# 51-2001-01-14_04_Power_Module_Schematic.net
KiCad netlist of a schematic drawn in Altium Designer
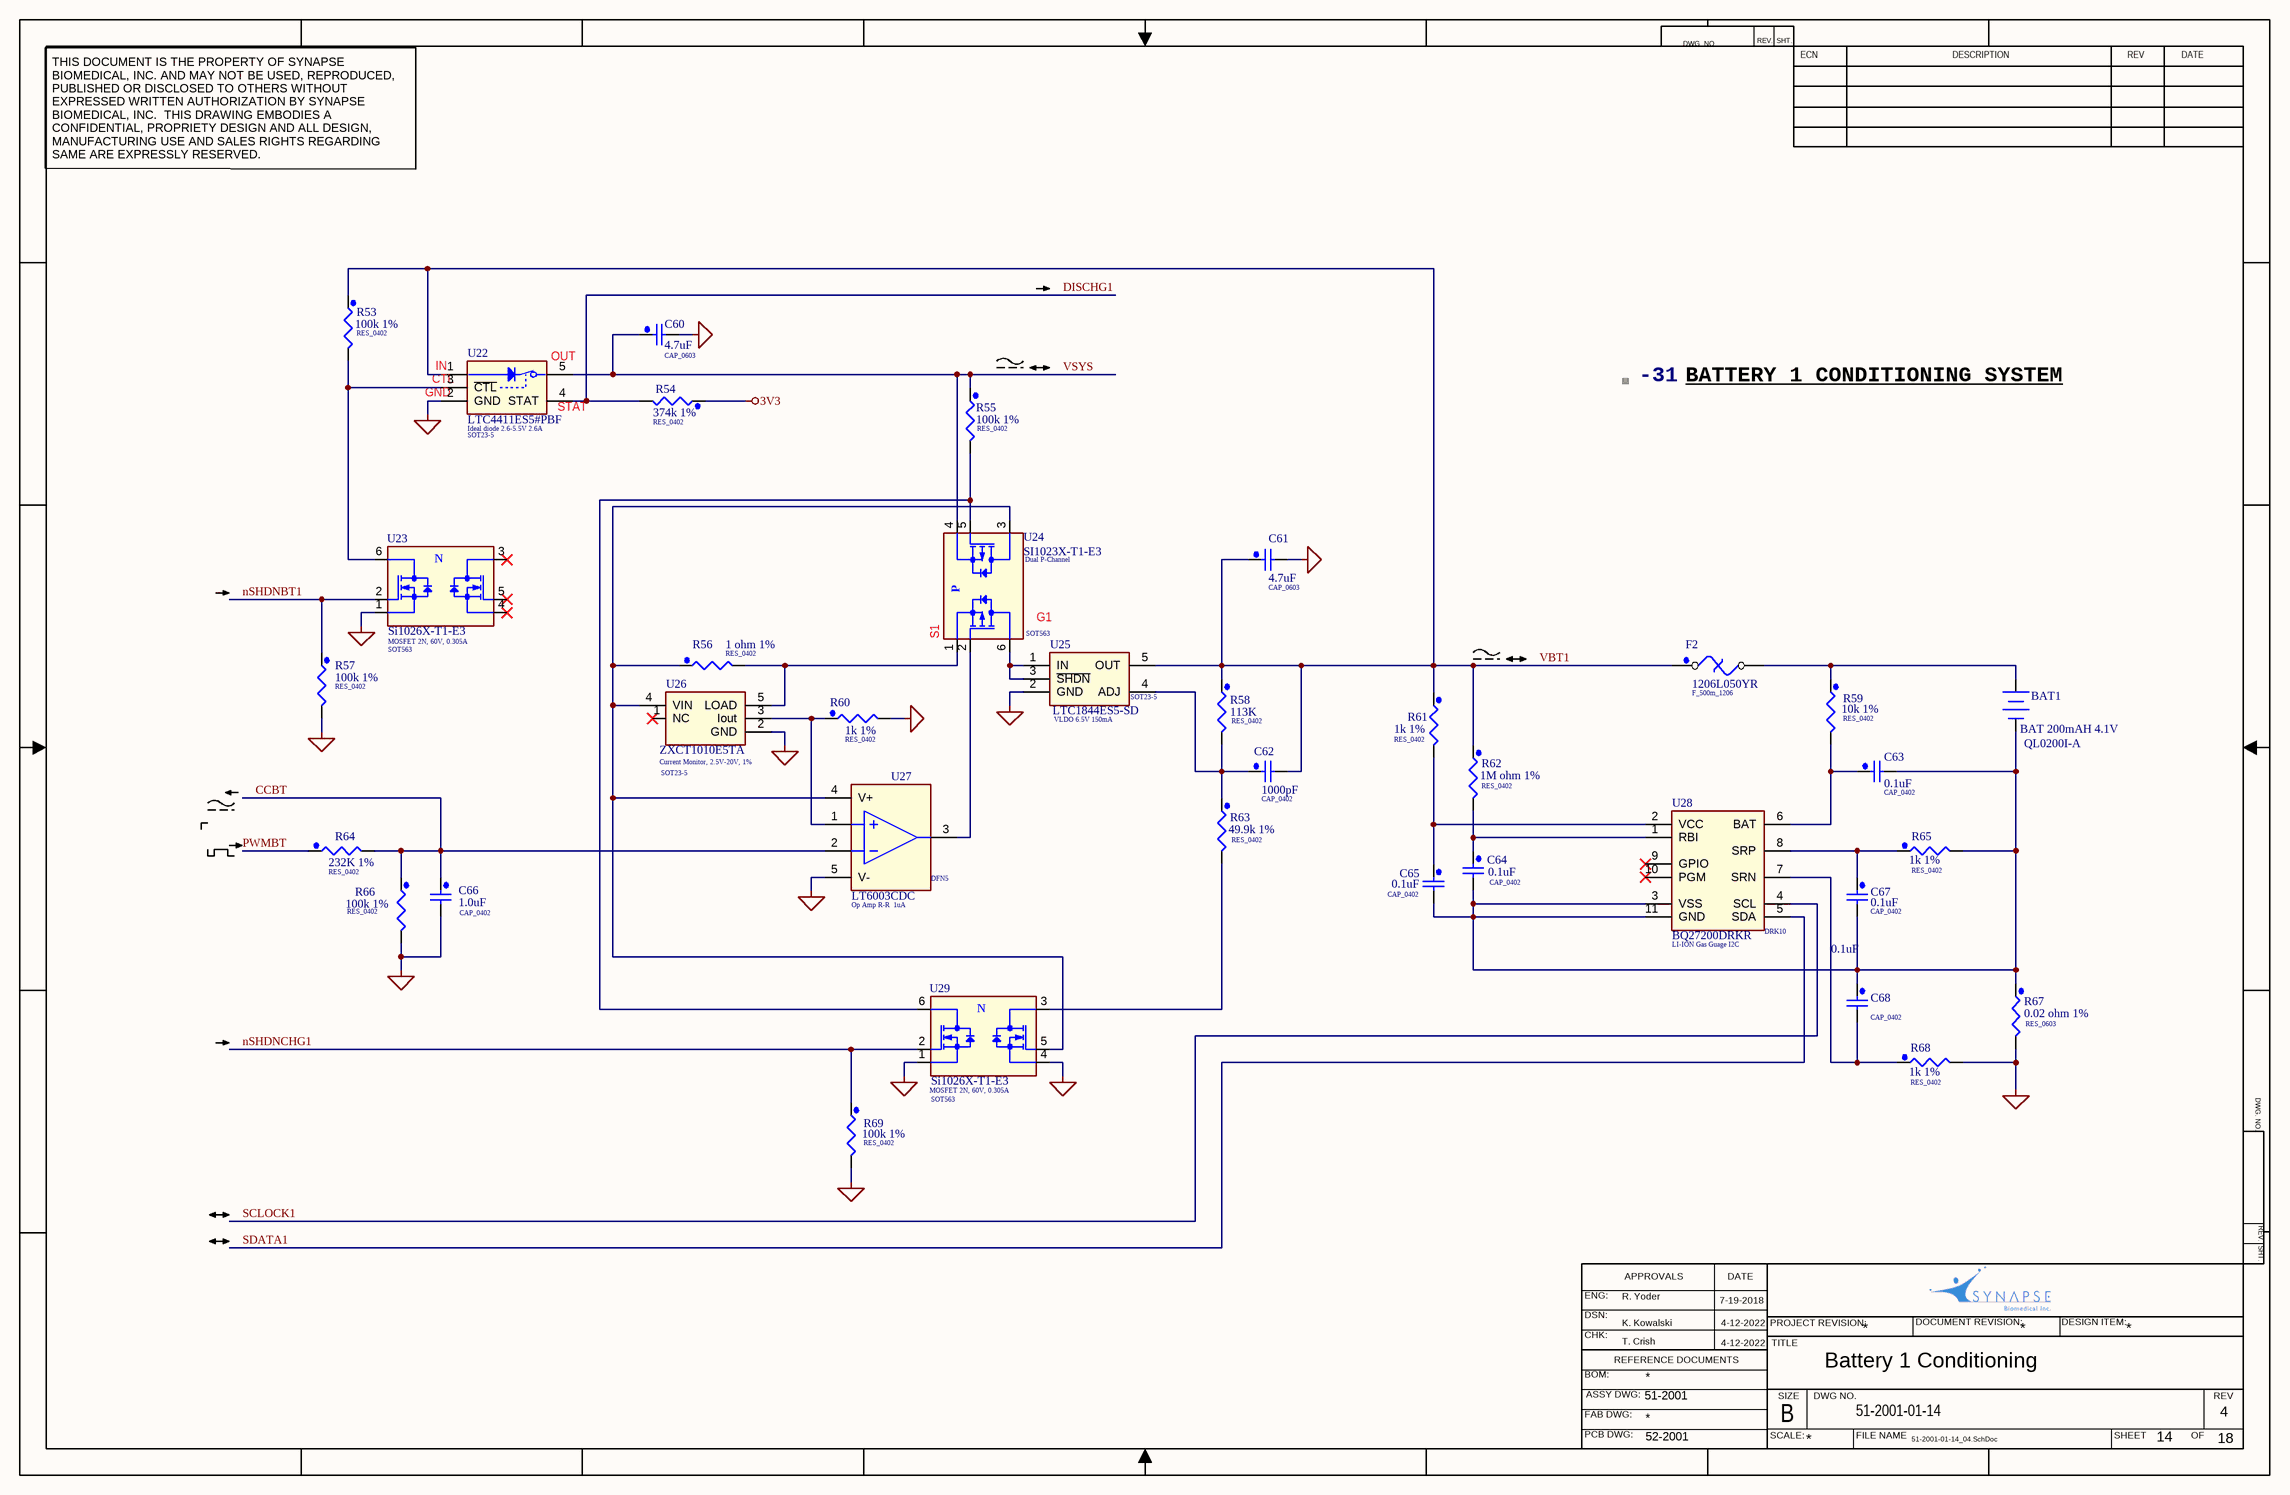
[diagram p0: 51-2001-01-14_04 Power Module Schematic.SchDoc]

(export (version "E")
  (design (tool "Eeschema 10.0.6"))
  (components
    (comp (ref "-31")
      (value "BOM_S1")
      (description "BOM item small graphic")
      (fields (field (name "XDESCRIPTION") "BATTERY 1 CONDITIONING SYSTEM"))
      (libsource (lib "BOM_sym") (part "BOM_S1"))
    )
    (comp (ref "BAT1")
      (value "BAT 200mAH 4.1V")
      (footprint "QL0200I-A")
      (description "Li-ion battery 200mAH 4.1V")
      (fields (field (name "MFR") "Quallion") (field (name "MPN") "QL0200I-A"))
      (libsource (lib "NNPS Integrated Parts") (part "QL0200I-A"))
    )
    (comp (ref "C60")
      (value "4.7uF")
      (footprint "CAP_0603")
      (description "4.7uF, 10V, X5R, 10%, 0603, RoHS")
      (fields
        (field (name "MFR") "Murata Electronics North America")
        (field (name "PACKAGEDESCRIPTION") "CAP_0603")
        (field (name "MPN") "GRM185R61A475KE11D")
      )
      (libsource (lib "NNPS Integrated Parts") (part "LMK107BJ475KA-T"))
    )
    (comp (ref "C61")
      (value "4.7uF")
      (footprint "CAP_0603")
      (description "4.7uF, 10V, X5R, 10%, 0603, RoHS")
      (fields
        (field (name "MFR") "Murata Electronics North America")
        (field (name "PACKAGEDESCRIPTION") "CAP_0603")
        (field (name "MPN") "GRM185R61A475KE11D")
      )
      (libsource (lib "NNPS Integrated Parts") (part "LMK107BJ475KA-T"))
    )
    (comp (ref "C62")
      (value "1000pF")
      (footprint "CAP_0402")
      (description "1000pF, 50V, C0G, 5%, 0402, RoHS")
      (fields
        (field (name "MFR") "Murata")
        (field (name "PACKAGEDESCRIPTION") "CAP_0402")
        (field (name "MPN") "GRM1555C1H102JA01D")
      )
      (libsource (lib "NNPS Integrated Parts") (part "GRM1555C1H102JA01D"))
    )
    (comp (ref "C63")
      (value "0.1uF")
      (footprint "CAP_0402")
      (description "0.1uF, 16V, X7R, 0402, RoHS")
      (fields
        (field (name "MFR") "Murata")
        (field (name "PACKAGEDESCRIPTION") "CAP_0402")
        (field (name "MPN") "GRM155R71C104KA88D")
      )
      (libsource (lib "NNPS Integrated Parts") (part "GRM155R71C104KA88D"))
    )
    (comp (ref "C64")
      (value "0.1uF")
      (footprint "CAP_0402")
      (description "0.1uF, 16V, X7R, 0402, RoHS")
      (fields
        (field (name "MFR") "Murata")
        (field (name "PACKAGEDESCRIPTION") "CAP_0402")
        (field (name "MPN") "GRM155R71C104KA88D")
      )
      (libsource (lib "NNPS Integrated Parts") (part "GRM155R71C104KA88D"))
    )
    (comp (ref "C65")
      (value "0.1uF")
      (footprint "CAP_0402")
      (description "0.1uF, 16V, X7R, 0402, RoHS")
      (fields
        (field (name "MFR") "Murata")
        (field (name "PACKAGEDESCRIPTION") "CAP_0402")
        (field (name "MPN") "GRM155R71C104KA88D")
      )
      (libsource (lib "NNPS Integrated Parts") (part "GRM155R71C104KA88D"))
    )
    (comp (ref "C66")
      (value "1.0uF")
      (footprint "CAP_0402")
      (description "1.0uF, 6.3V, X5R, 20%, 0402, RoHS")
      (fields
        (field (name "MFR") "Murata Electronics North America")
        (field (name "PACKAGEDESCRIPTION") "CAP_0402")
        (field (name "MPN") "GRM152R60J105ME15D")
      )
      (libsource (lib "NNPS Integrated Parts") (part "ECJ-0EB0J105M"))
    )
    (comp (ref "C67")
      (value "0.1uF")
      (footprint "CAP_0402")
      (description "0.1uF, 16V, X7R, 0402, RoHS")
      (fields
        (field (name "MFR") "Murata")
        (field (name "PACKAGEDESCRIPTION") "CAP_0402")
        (field (name "MPN") "GRM155R71C104KA88D")
      )
      (libsource (lib "NNPS Integrated Parts") (part "GRM155R71C104KA88D"))
    )
    (comp (ref "C68")
      (value "0.1uF")
      (footprint "CAP_0402")
      (description "0.1uF, 16V, X7R, 0402, RoHS")
      (fields
        (field (name "MFR") "Murata")
        (field (name "PACKAGEDESCRIPTION") "CAP_0402")
        (field (name "MPN") "GRM155R71C104KA88D")
      )
      (libsource (lib "NNPS Integrated Parts") (part "GRM155R71C104KA88D"))
    )
    (comp (ref "F2")
      (value "F_500m_1206")
      (footprint "FUSE_1206")
      (description "PTC Resettable, 500mA, 0.4 ohm,  6V, 1206, RoHS")
      (fields
        (field (name "MFR") "Littelfuse")
        (field (name "PACKAGEDESCRIPTION") "F_500m_1206")
        (field (name "MPN") "1206L050YR")
      )
      (libsource (lib "NNPS Integrated Parts") (part "1206L050YR"))
    )
    (comp (ref "R53")
      (value "100k 1%")
      (footprint "RES_0402")
      (description "100k ohm, 1%, 1/16W, smd, 0402, RoHS")
      (fields
        (field (name "MFR") "Vishay Dale")
        (field (name "PACKAGEDESCRIPTION") "RES_0402")
        (field (name "MPN") "CRCW0402100KFKED")
      )
      (libsource (lib "NNPS Integrated Parts") (part "MCR01MZPF1003"))
    )
    (comp (ref "R54")
      (value "374k 1%")
      (footprint "RES_0402")
      (description "374k ohm, 1%, 1/16W, 0402,RoHS")
      (fields
        (field (name "MFR") "Vishay Dale")
        (field (name "PACKAGEDESCRIPTION") "RES_0402")
        (field (name "MPN") "CRCW0402374KFKED")
      )
      (libsource (lib "NNPS Integrated Parts") (part "CRCW0402374KFKED"))
    )
    (comp (ref "R55")
      (value "100k 1%")
      (footprint "RES_0402")
      (description "100k ohm, 1%, 1/16W, smd, 0402, RoHS")
      (fields
        (field (name "MFR") "Vishay Dale")
        (field (name "PACKAGEDESCRIPTION") "RES_0402")
        (field (name "MPN") "CRCW0402100KFKED")
      )
      (libsource (lib "NNPS Integrated Parts") (part "MCR01MZPF1003"))
    )
    (comp (ref "R56")
      (value "1 ohm 1%")
      (footprint "RES_0402")
      (description "1.0 ohm, 1%, 1/16W, 0402, RoHS")
      (fields
        (field (name "MFR") "Vishay")
        (field (name "PACKAGEDESCRIPTION") "RES_0402")
        (field (name "MPN") "CRCW04021R00FNED")
      )
      (libsource (lib "NNPS Integrated Parts") (part "CRCW04021R00FNED"))
    )
    (comp (ref "R57")
      (value "100k 1%")
      (footprint "RES_0402")
      (description "100k ohm, 1%, 1/16W, smd, 0402, RoHS")
      (fields
        (field (name "MFR") "Vishay Dale")
        (field (name "PACKAGEDESCRIPTION") "RES_0402")
        (field (name "MPN") "CRCW0402100KFKED")
      )
      (libsource (lib "NNPS Integrated Parts") (part "MCR01MZPF1003"))
    )
    (comp (ref "R58")
      (value "113K")
      (footprint "RES_0402")
      (description "113k ohm, 1%, 1/16W, 0402, RoHS")
      (fields
        (field (name "MFR") "Vishay Dale")
        (field (name "PACKAGEDESCRIPTION") "RES_0402")
        (field (name "MPN") "CRCW0402113KFKED")
      )
      (libsource (lib "NNPS Integrated Parts") (part "ERJ-2RKF1133X"))
    )
    (comp (ref "R59")
      (value "10k 1%")
      (footprint "RES_0402")
      (description "10.0k ohm, 1%, 1/16W, smd, 0402, RoHS")
      (fields
        (field (name "MFR") "Vishay Dale")
        (field (name "PACKAGEDESCRIPTION") "RES_0402")
        (field (name "MPN") "CRCW040210K0FKED")
      )
      (libsource (lib "NNPS Integrated Parts") (part "MCR01MZPF1002"))
    )
    (comp (ref "R60")
      (value "1k 1%")
      (footprint "RES_0402")
      (description "1.0k ohm 1% 1/16W smd 0402 RoHS")
      (fields
        (field (name "MFR") "Vishay Dale")
        (field (name "PACKAGEDESCRIPTION") "RES_0402")
        (field (name "MPN") "CRCW04021K00FKED")
      )
      (libsource (lib "NNPS Integrated Parts") (part "MCR01MZPF1001"))
    )
    (comp (ref "R61")
      (value "1k 1%")
      (footprint "RES_0402")
      (description "1.0k ohm 1% 1/16W smd 0402 RoHS")
      (fields
        (field (name "MFR") "Vishay Dale")
        (field (name "PACKAGEDESCRIPTION") "RES_0402")
        (field (name "MPN") "CRCW04021K00FKED")
      )
      (libsource (lib "NNPS Integrated Parts") (part "MCR01MZPF1001"))
    )
    (comp (ref "R62")
      (value "1M ohm 1%")
      (footprint "RES_0402")
      (description "1M ohm, 1/16W, 1%, 0402, RoHS")
      (fields
        (field (name "MFR") "Vishay Dale")
        (field (name "PACKAGEDESCRIPTION") "RES_0402")
        (field (name "MPN") "CRCW04021M00FKED")
      )
      (libsource (lib "NNPS Integrated Parts") (part "MCR01MZPF1004"))
    )
    (comp (ref "R63")
      (value "49.9k 1%")
      (footprint "RES_0402")
      (description "49.9k ohm, 1%, 1/16W, 0402, RoHS")
      (fields
        (field (name "MFR") "Vishay Dale")
        (field (name "PACKAGEDESCRIPTION") "RES_0402")
        (field (name "MPN") "CRCW040249K9FKED")
      )
      (libsource (lib "NNPS Integrated Parts") (part "MCR01MZPF4992"))
    )
    (comp (ref "R64")
      (value "232K 1%")
      (footprint "RES_0402")
      (description "232k, 1%, 1/16W, 0402, RoHS")
      (fields
        (field (name "MFR") "Vishay Dale")
        (field (name "PACKAGEDESCRIPTION") "RES_0402")
        (field (name "MPN") "CRCW0402232KFKED")
      )
      (libsource (lib "NNPS Integrated Parts") (part "CRCW0402232KFKED"))
    )
    (comp (ref "R65")
      (value "1k 1%")
      (footprint "RES_0402")
      (description "1.0k ohm 1% 1/16W smd 0402 RoHS")
      (fields
        (field (name "MFR") "Vishay Dale")
        (field (name "PACKAGEDESCRIPTION") "RES_0402")
        (field (name "MPN") "CRCW04021K00FKED")
      )
      (libsource (lib "NNPS Integrated Parts") (part "MCR01MZPF1001"))
    )
    (comp (ref "R66")
      (value "100k 1%")
      (footprint "RES_0402")
      (description "100k ohm, 1%, 1/16W, smd, 0402, RoHS")
      (fields
        (field (name "MFR") "Vishay Dale")
        (field (name "PACKAGEDESCRIPTION") "RES_0402")
        (field (name "MPN") "CRCW0402100KFKED")
      )
      (libsource (lib "NNPS Integrated Parts") (part "MCR01MZPF1003"))
    )
    (comp (ref "R67")
      (value "0.02 ohm 1%")
      (footprint "RES_0603")
      (description "0.02 ohm, 1%, 1/10W, 0603, RoHS")
      (fields
        (field (name "MFR") "Vishay Dale")
        (field (name "PACKAGEDESCRIPTION") "RES_0603")
        (field (name "MPN") "WSL0603R0200FEA")
      )
      (libsource (lib "NNPS Integrated Parts") (part "WSL0603R0200FEA"))
    )
    (comp (ref "R68")
      (value "1k 1%")
      (footprint "RES_0402")
      (description "1.0k ohm 1% 1/16W smd 0402 RoHS")
      (fields
        (field (name "MFR") "Vishay Dale")
        (field (name "PACKAGEDESCRIPTION") "RES_0402")
        (field (name "MPN") "CRCW04021K00FKED")
      )
      (libsource (lib "NNPS Integrated Parts") (part "MCR01MZPF1001"))
    )
    (comp (ref "R69")
      (value "100k 1%")
      (footprint "RES_0402")
      (description "100k ohm, 1%, 1/16W, smd, 0402, RoHS")
      (fields
        (field (name "MFR") "Vishay Dale")
        (field (name "PACKAGEDESCRIPTION") "RES_0402")
        (field (name "MPN") "CRCW0402100KFKED")
      )
      (libsource (lib "NNPS Integrated Parts") (part "MCR01MZPF1003"))
    )
    (comp (ref "U22")
      (value "Ideal diode 2.6-5.5V 2.6A")
      (footprint "SOT23-5")
      (description "Ideal diode, 2.6-5.5V, 2.6A, SOT23-5, RoHS")
      (fields
        (field (name "MFR") "Linear Technology")
        (field (name "PACKAGEDESCRIPTION") "SOT23-5")
        (field (name "MPN") "LTC4411ES5#PBF")
      )
      (libsource (lib "NNPS Integrated Parts") (part "LTC4411ES5"))
    )
    (comp (ref "U23")
      (value "MOSFET 2N, 60V, 0.305A")
      (footprint "SOT-563")
      (description "MOSFET 2N, 60V, 0.305A, RoHS")
      (fields
        (field (name "MFR") "Vishay Siliconix")
        (field (name "PACKAGEDESCRIPTION") "SOT563")
        (field (name "MPN") "Si1026X-T1-E3")
      )
      (libsource (lib "NNPS Integrated Parts") (part "Si1026X-T1-E3"))
    )
    (comp (ref "U24")
      (value "Dual P-Channel")
      (footprint "SOT-563")
      (description "Dual P-Channel Mosfet, SOT563, RoHS")
      (fields
        (field (name "MFR") "Vishay Siliconix")
        (field (name "PACKAGEDESCRIPTION") "SOT563")
        (field (name "MPN") "SI1023X-T1-E3")
      )
      (libsource (lib "NNPS Integrated Parts") (part "SI1023X-T1-E3"))
    )
    (comp (ref "U25")
      (value "VLDO 6.5V 150mA")
      (footprint "SOT23-5")
      (description "VLDO, 150mA, SOT23-5, RoHS")
      (fields
        (field (name "MFR") "Linear Technology")
        (field (name "PACKAGEDESCRIPTION") "SOT23-5")
        (field (name "MPN") "LTC1844ES5-SD")
      )
      (libsource (lib "NNPS Integrated Parts") (part "LTC1844ES5-SD"))
    )
    (comp (ref "U26")
      (value "Current Monitor, 2.5V-20V, 1%")
      (footprint "SOT23-5")
      (description "Current Monitor, 2.5V-20V, 1%, RoHS")
      (fields
        (field (name "MFR") "Diodes Incorporated")
        (field (name "PACKAGEDESCRIPTION") "SOT23-5")
        (field (name "MPN") "ZXCT1010E5TA")
      )
      (libsource (lib "NNPS Integrated Parts") (part "ZXCT1010E5TA"))
    )
    (comp (ref "U27")
      (value "Op Amp R-R  1uA")
      (footprint "DFN4")
      (description "Op Amp, R-R, 1uA, RoHS")
      (fields
        (field (name "PACKAGEDESCRIPTION") "DFN5")
        (field (name "MFR") "Linear Technology")
        (field (name "MPN") "LT6003CDC")
      )
      (libsource (lib "NNPS Integrated Parts") (part "LT6003CDC"))
    )
    (comp (ref "U28")
      (value "LI-ION Gas Guage I2C")
      (footprint "QFN10")
      (description "LI-ION Gas Guage, I2C, QFN10, RoHS")
      (fields
        (field (name "MFR") "Texas Instruments")
        (field (name "PACKAGEDESCRIPTION") "DRK10")
        (field (name "MPN") "BQ27200DRKR")
      )
      (libsource (lib "NNPS Integrated Parts") (part "BQ27200DRKR"))
    )
    (comp (ref "U29")
      (value "MOSFET 2N, 60V, 0.305A")
      (footprint "SOT-563")
      (description "MOSFET 2N, 60V, 0.305A, RoHS")
      (fields
        (field (name "MFR") "Vishay Siliconix")
        (field (name "PACKAGEDESCRIPTION") "SOT563")
        (field (name "MPN") "Si1026X-T1-E3")
      )
      (libsource (lib "NNPS Integrated Parts") (part "Si1026X-T1-E3"))
    )
  )
  (nets
    (net (code "1") (name "/CCBT") (class "Default")
      (node (ref "C66") (pin "1") (pinfunction "1_1") (pintype "passive"))
      (node (ref "R64") (pin "2") (pinfunction "2_2") (pintype "passive"))
      (node (ref "R66") (pin "1") (pinfunction "1_1") (pintype "passive"))
      (node (ref "U27") (pin "2") (pinfunction "-IN_2") (pintype "passive"))
    )
    (net (code "2") (name "/DISCHG1") (class "Default")
      (node (ref "R54") (pin "2") (pinfunction "2_2") (pintype "passive"))
      (node (ref "U22") (pin "4") (pinfunction "STAT_4") (pintype "passive"))
    )
    (net (code "3") (name "/PWMBT") (class "Default")
      (node (ref "R64") (pin "1") (pinfunction "1_1") (pintype "passive"))
    )
    (net (code "4") (name "/SCLOCK1") (class "Default")
      (node (ref "U28") (pin "4") (pinfunction "SCL_4") (pintype "passive"))
    )
    (net (code "5") (name "/SDATA1") (class "Default")
      (node (ref "U28") (pin "5") (pinfunction "SDA_5") (pintype "passive"))
    )
    (net (code "6") (name "/VBT1") (class "Default")
      (node (ref "C61") (pin "1") (pinfunction "1_1") (pintype "passive"))
      (node (ref "C62") (pin "2") (pinfunction "2_2") (pintype "passive"))
      (node (ref "F2") (pin "1") (pinfunction "1_1") (pintype "passive"))
      (node (ref "R53") (pin "1") (pinfunction "1_1") (pintype "passive"))
      (node (ref "R58") (pin "1") (pinfunction "1_1") (pintype "passive"))
      (node (ref "R61") (pin "1") (pinfunction "1_1") (pintype "passive"))
      (node (ref "R62") (pin "1") (pinfunction "1_1") (pintype "passive"))
      (node (ref "U22") (pin "1") (pinfunction "IN_1") (pintype "passive"))
      (node (ref "U25") (pin "5") (pinfunction "OUT_5") (pintype "passive"))
    )
    (net (code "7") (name "/VSYS") (class "Default")
      (node (ref "C60") (pin "1") (pinfunction "1_1") (pintype "passive"))
      (node (ref "R55") (pin "1") (pinfunction "1_1") (pintype "passive"))
      (node (ref "U22") (pin "5") (pinfunction "OUT_5") (pintype "passive"))
      (node (ref "U24") (pin "4") (pinfunction "S2_4") (pintype "passive"))
    )
    (net (code "8") (name "/nSHDNBT1") (class "Default")
      (node (ref "R57") (pin "1") (pinfunction "1_1") (pintype "passive"))
      (node (ref "U23") (pin "2") (pinfunction "G1_2") (pintype "passive"))
    )
    (net (code "9") (name "/nSHDNCHG1") (class "Default")
      (node (ref "R69") (pin "1") (pinfunction "1_1") (pintype "passive"))
      (node (ref "U29") (pin "2") (pinfunction "G1_2") (pintype "passive"))
    )
    (net (code "10") (name "3V3") (class "Default")
      (node (ref "R54") (pin "1") (pinfunction "1_1") (pintype "passive"))
    )
    (net (code "11") (name "GND") (class "Default")
      (node (ref "C60") (pin "2") (pinfunction "2_2") (pintype "passive"))
      (node (ref "C61") (pin "2") (pinfunction "2_2") (pintype "passive"))
      (node (ref "C66") (pin "2") (pinfunction "2_2") (pintype "passive"))
      (node (ref "R57") (pin "2") (pinfunction "2_2") (pintype "passive"))
      (node (ref "R60") (pin "2") (pinfunction "2_2") (pintype "passive"))
      (node (ref "R66") (pin "2") (pinfunction "2_2") (pintype "passive"))
      (node (ref "R67") (pin "2") (pinfunction "2_2") (pintype "passive"))
      (node (ref "R68") (pin "2") (pinfunction "2_2") (pintype "passive"))
      (node (ref "R69") (pin "2") (pinfunction "2_2") (pintype "passive"))
      (node (ref "U22") (pin "2") (pinfunction "GND_2") (pintype "passive"))
      (node (ref "U23") (pin "1") (pinfunction "S1_1") (pintype "passive"))
      (node (ref "U25") (pin "2") (pinfunction "GND_2") (pintype "passive"))
      (node (ref "U26") (pin "2") (pinfunction "GND_2") (pintype "power_in"))
      (node (ref "U27") (pin "5") (pinfunction "V-_5") (pintype "power_in"))
      (node (ref "U29") (pin "1") (pinfunction "S1_1") (pintype "passive"))
      (node (ref "U29") (pin "4") (pinfunction "S2_4") (pintype "passive"))
    )
    (net (code "12") (name "Net-(BAT1-+)") (class "Default")
      (node (ref "BAT1") (pin "1") (pinfunction "+_1") (pintype "passive"))
      (node (ref "F2") (pin "2") (pinfunction "2_2") (pintype "passive"))
      (node (ref "R59") (pin "1") (pinfunction "1_1") (pintype "passive"))
    )
    (net (code "13") (name "Net-(BAT1--)") (class "Default")
      (node (ref "BAT1") (pin "2") (pinfunction "-_2") (pintype "passive"))
      (node (ref "C63") (pin "2") (pinfunction "2_2") (pintype "passive"))
      (node (ref "C64") (pin "2") (pinfunction "2_2") (pintype "passive"))
      (node (ref "C65") (pin "2") (pinfunction "2_2") (pintype "passive"))
      (node (ref "C67") (pin "2") (pinfunction "2_2") (pintype "passive"))
      (node (ref "C68") (pin "1") (pinfunction "1_1") (pintype "passive"))
      (node (ref "R65") (pin "2") (pinfunction "2_2") (pintype "passive"))
      (node (ref "R67") (pin "1") (pinfunction "1_1") (pintype "passive"))
      (node (ref "U28") (pin "11") (pinfunction "GND_11") (pintype "passive"))
      (node (ref "U28") (pin "3") (pinfunction "VSS_3") (pintype "passive"))
    )
    (net (code "14") (name "Net-(U22-~{CTL})") (class "Default")
      (node (ref "R53") (pin "2") (pinfunction "2_2") (pintype "passive"))
      (node (ref "U22") (pin "3") (pinfunction "~{CTL}_3") (pintype "passive"))
      (node (ref "U23") (pin "6") (pinfunction "D1_6") (pintype "passive"))
    )
    (net (code "15") (name "Net-(U24-D1)") (class "Default")
      (node (ref "U24") (pin "6") (pinfunction "D1_6") (pintype "passive"))
      (node (ref "U25") (pin "1") (pinfunction "IN_1") (pintype "passive"))
      (node (ref "U25") (pin "3") (pinfunction "SHDN_3") (pintype "passive"))
    )
    (net (code "16") (name "Net-(U24-D2)") (class "Default")
      (node (ref "R56") (pin "1") (pinfunction "1_1") (pintype "passive"))
      (node (ref "U24") (pin "3") (pinfunction "D2_3") (pintype "passive"))
      (node (ref "U26") (pin "4") (pinfunction "VIN_4") (pintype "power_in"))
      (node (ref "U27") (pin "4") (pinfunction "V+_4") (pintype "power_in"))
      (node (ref "U29") (pin "5") (pinfunction "G2_5") (pintype "passive"))
    )
    (net (code "17") (name "Net-(U24-G1)") (class "Default")
      (node (ref "U24") (pin "2") (pinfunction "G1_2") (pintype "passive"))
      (node (ref "U27") (pin "3") (pinfunction "OUT_A_3") (pintype "passive"))
    )
    (net (code "18") (name "Net-(U24-G2)") (class "Default")
      (node (ref "R55") (pin "2") (pinfunction "2_2") (pintype "passive"))
      (node (ref "U24") (pin "5") (pinfunction "G2_5") (pintype "passive"))
      (node (ref "U29") (pin "6") (pinfunction "D1_6") (pintype "passive"))
    )
    (net (code "19") (name "Net-(U24-S1)") (class "Default")
      (node (ref "R56") (pin "2") (pinfunction "2_2") (pintype "passive"))
      (node (ref "U24") (pin "1") (pinfunction "S1_1") (pintype "passive"))
      (node (ref "U26") (pin "5") (pinfunction "LOAD_5") (pintype "passive"))
    )
    (net (code "20") (name "Net-(U25-ADJ)") (class "Default")
      (node (ref "C62") (pin "1") (pinfunction "1_1") (pintype "passive"))
      (node (ref "R58") (pin "2") (pinfunction "2_2") (pintype "passive"))
      (node (ref "R63") (pin "1") (pinfunction "1_1") (pintype "passive"))
      (node (ref "U25") (pin "4") (pinfunction "ADJ_4") (pintype "passive"))
    )
    (net (code "21") (name "Net-(U26-Iout)") (class "Default")
      (node (ref "R60") (pin "1") (pinfunction "1_1") (pintype "passive"))
      (node (ref "U26") (pin "3") (pinfunction "Iout_3") (pintype "passive"))
      (node (ref "U27") (pin "1") (pinfunction "+IN_1") (pintype "passive"))
    )
    (net (code "22") (name "Net-(U28-BAT)") (class "Default")
      (node (ref "C63") (pin "1") (pinfunction "1_1") (pintype "passive"))
      (node (ref "R59") (pin "2") (pinfunction "2_2") (pintype "passive"))
      (node (ref "U28") (pin "6") (pinfunction "BAT_6") (pintype "passive"))
    )
    (net (code "23") (name "Net-(U28-RBI)") (class "Default")
      (node (ref "C64") (pin "1") (pinfunction "1_1") (pintype "passive"))
      (node (ref "R62") (pin "2") (pinfunction "2_2") (pintype "passive"))
      (node (ref "U28") (pin "1") (pinfunction "RBI_1") (pintype "passive"))
    )
    (net (code "24") (name "Net-(U28-SRN)") (class "Default")
      (node (ref "C68") (pin "2") (pinfunction "2_2") (pintype "passive"))
      (node (ref "R68") (pin "1") (pinfunction "1_1") (pintype "passive"))
      (node (ref "U28") (pin "7") (pinfunction "SRN_7") (pintype "passive"))
    )
    (net (code "25") (name "Net-(U28-SRP)") (class "Default")
      (node (ref "C67") (pin "1") (pinfunction "1_1") (pintype "passive"))
      (node (ref "R65") (pin "1") (pinfunction "1_1") (pintype "passive"))
      (node (ref "U28") (pin "8") (pinfunction "SRP_8") (pintype "passive"))
    )
    (net (code "26") (name "Net-(U28-VCC)") (class "Default")
      (node (ref "C65") (pin "1") (pinfunction "1_1") (pintype "passive"))
      (node (ref "R61") (pin "2") (pinfunction "2_2") (pintype "passive"))
      (node (ref "U28") (pin "2") (pinfunction "VCC_2") (pintype "passive"))
    )
    (net (code "27") (name "Net-(U29-D2)") (class "Default")
      (node (ref "R63") (pin "2") (pinfunction "2_2") (pintype "passive"))
      (node (ref "U29") (pin "3") (pinfunction "D2_3") (pintype "passive"))
    )
    (net (code "28") (name "unconnected-(U23-D2-Pad3)") (class "Default")
      (node (ref "U23") (pin "3") (pinfunction "D2_3") (pintype "passive+no_connect"))
    )
    (net (code "29") (name "unconnected-(U23-G2-Pad5)") (class "Default")
      (node (ref "U23") (pin "5") (pinfunction "G2_5") (pintype "passive+no_connect"))
    )
    (net (code "30") (name "unconnected-(U23-S2-Pad4)") (class "Default")
      (node (ref "U23") (pin "4") (pinfunction "S2_4") (pintype "passive+no_connect"))
    )
    (net (code "31") (name "unconnected-(U26-NC-Pad1)") (class "Default")
      (node (ref "U26") (pin "1") (pinfunction "NC_1") (pintype "tri_state+no_connect"))
    )
    (net (code "32") (name "unconnected-(U28-GPIO-Pad9)") (class "Default")
      (node (ref "U28") (pin "9") (pinfunction "GPIO_9") (pintype "passive+no_connect"))
    )
    (net (code "33") (name "unconnected-(U28-PGM-Pad10)") (class "Default")
      (node (ref "U28") (pin "10") (pinfunction "PGM_10") (pintype "passive+no_connect"))
    )
  )
)
